# MolkkyV2.net
KiCad netlist of a schematic drawn in Altium Designer
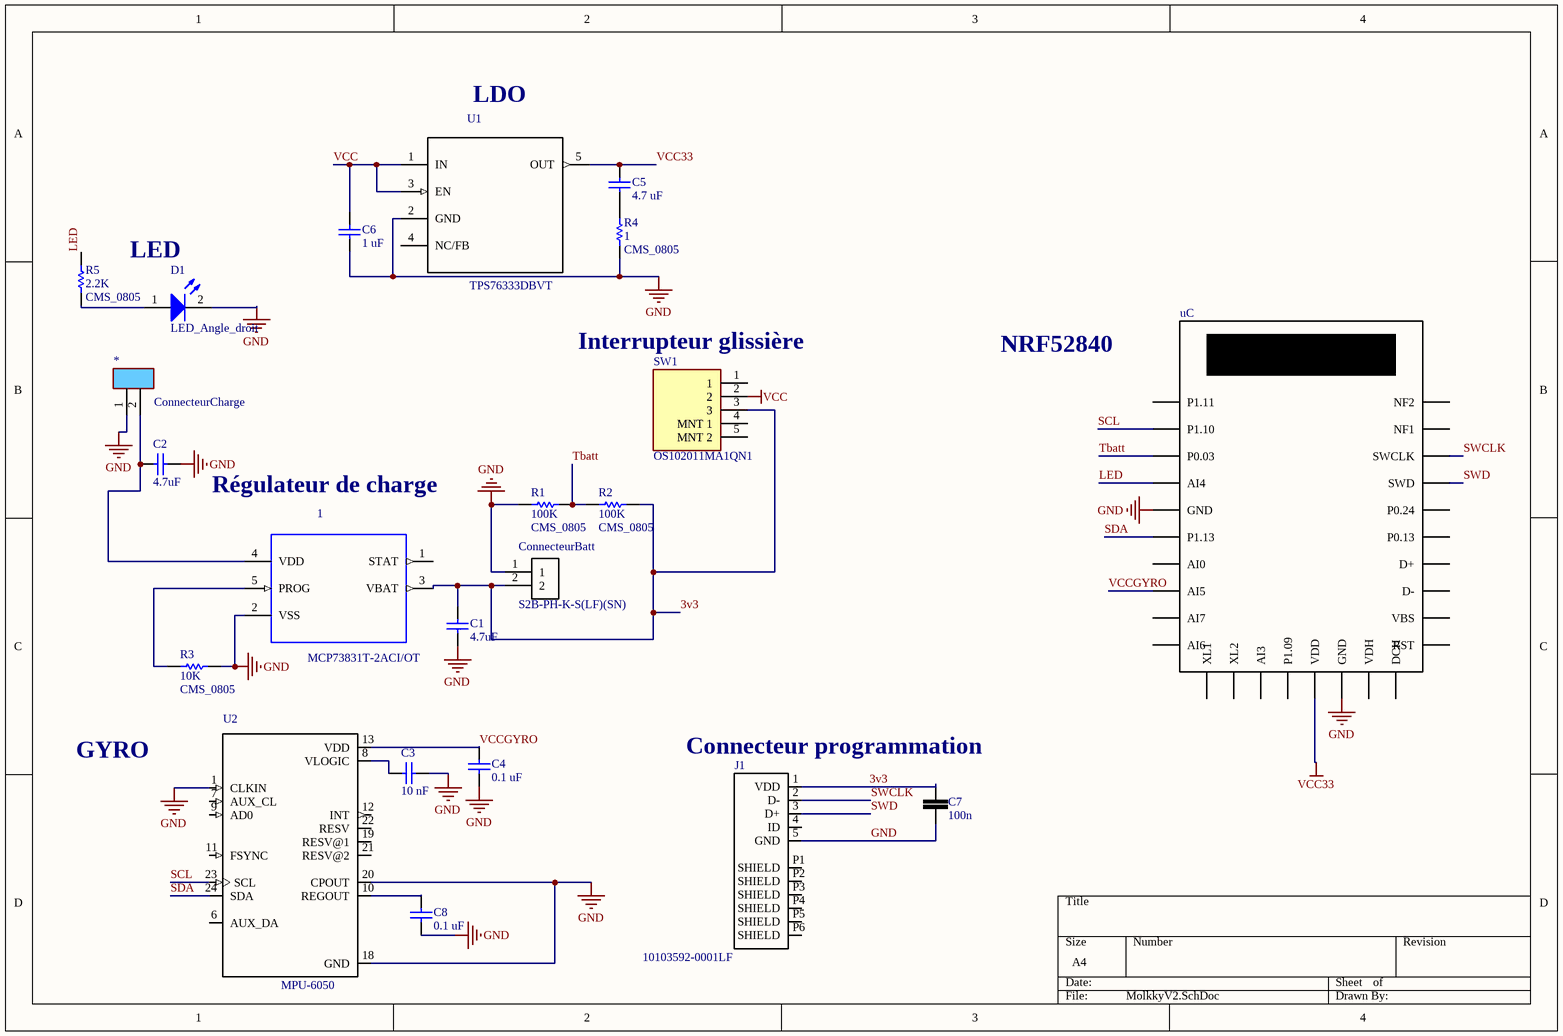
[diagram p0: MolkkyV2.SchDoc]

(export (version "E")
  (design (tool "Eeschema 10.0.6"))
  (components
    (comp (ref "*")
      (value "ConnecteurCharge")
      (footprint "BARRETTE 2")
      (libsource (lib "connecteurs") (part "Barrette 2"))
    )
    (comp (ref "1")
      (value "MCP73831T-2ACI/OT")
      (footprint "*SOT95P280X145-5N")
      (description "MCP73831 Series Single-Cell Li-Ion/Li-Polymer Battery Charge Controller SOT-23-5")
      (fields (field (name "MF") "Microchip"))
      (libsource (lib "MCP73831T-2ACI_OT") (part "MCP73831T-2ACI/OT"))
    )
    (comp (ref "C1")
      (value "4.7uF")
      (footprint "CONDENSATEUR_CMS_0805")
      (description "CONDENSATEUR CMS CERAMIQUE 0805")
      (fields (field (name "Comment") "CMS_0805"))
      (libsource (lib "composants passifs") (part "CONDENSATEUR_CMS_CER_0805"))
    )
    (comp (ref "C2")
      (value "4.7uF")
      (footprint "CONDENSATEUR_CMS_0805")
      (description "CONDENSATEUR CMS CERAMIQUE 0805")
      (fields (field (name "Comment") "CMS_0805"))
      (libsource (lib "composants passifs") (part "CONDENSATEUR_CMS_CER_0805"))
    )
    (comp (ref "C3")
      (value "10 nF")
      (footprint "CONDENSATEUR_CMS_0805")
      (description "CONDENSATEUR CMS CERAMIQUE 0805")
      (fields (field (name "Comment") "CMS_0805"))
      (libsource (lib "composants passifs") (part "CONDENSATEUR_CMS_CER_0805"))
    )
    (comp (ref "C4")
      (value "0.1 uF")
      (footprint "CONDENSATEUR_CMS_0805")
      (description "CONDENSATEUR CMS CERAMIQUE 0805")
      (fields (field (name "Comment") "CMS_0805"))
      (libsource (lib "composants passifs") (part "CONDENSATEUR_CMS_CER_0805"))
    )
    (comp (ref "C5")
      (value "4.7 uF")
      (footprint "CONDENSATEUR_CMS_0805")
      (description "CONDENSATEUR CMS CERAMIQUE 0805")
      (fields (field (name "Comment") "CMS_0805"))
      (libsource (lib "composants passifs") (part "CONDENSATEUR_CMS_CER_0805"))
    )
    (comp (ref "C6")
      (value "1 uF")
      (footprint "CONDENSATEUR_CMS_0805")
      (description "CONDENSATEUR CMS CERAMIQUE 0805")
      (fields (field (name "Comment") "CMS_0805"))
      (libsource (lib "composants passifs") (part "CONDENSATEUR_CMS_CER_0805"))
    )
    (comp (ref "C7")
      (value "100n")
      (footprint "CAPC2013X100N-0805-NoOverlay")
      (fields
        (field (name "MANUFACTURER") "Yageo")
        (field (name "MANUFACTURER PART NUMBER") "CC0805KRX7R9BB104")
        (field (name "TOLERANCE") "10%")
      )
      (libsource (lib "capacitors") (part "0100000001868"))
    )
    (comp (ref "C8")
      (value "0.1 uF")
      (footprint "CONDENSATEUR_CMS_0805")
      (description "CONDENSATEUR CMS CERAMIQUE 0805")
      (fields (field (name "Comment") "CMS_0805"))
      (libsource (lib "composants passifs") (part "CONDENSATEUR_CMS_CER_0805"))
    )
    (comp (ref "ConnecteurBatt")
      (value "S2B-PH-K-S(LF)(SN)")
      (footprint "*JST_S2B-PH-K-S(LF)(SN)")
      (description "PH Series 2 Position 2.0 mm Through Hole Side Entry Shrouded Header")
      (fields (field (name "MP") "S2B-PH-K-S_LF__SN_") (field (name "MF") "JST Sales"))
      (libsource (lib "S2B-PH-K-S_LF__SN_") (part "S2B-PH-K-S(LF)(SN)"))
    )
    (comp (ref "D1")
      (value "LED_3MM")
      (footprint "LED_Angle_droit")
      (description "LED Angle droit - ROUGE")
      (fields (field (name "TYPE") "LED_Angle_droit"))
      (libsource (lib "affichage") (part "LED Angle droit"))
    )
    (comp (ref "J1")
      (value "10103592-0001LF")
      (footprint "*AMPHENOL_10103592-0001LF_10103592-0001LF(Primary)")
      (description "Micro Usb, 2.0 Type b, Rcpt, Smt")
      (fields (field (name "MF") "Amphenol ICC"))
      (libsource (lib "10103592-0001LF") (part "10103592-0001LF"))
    )
    (comp (ref "R1")
      (value "100K")
      (footprint "RESISTANCE_CMS_0805")
      (description "RESISTANCE CMS 0805")
      (fields (field (name "TYPE") "CMS_0805") (field (name "Comment") "RESISTANCE_CMS_0805"))
      (libsource (lib "composants passifs") (part "RESISTANCE_CMS_0805"))
    )
    (comp (ref "R2")
      (value "100K")
      (footprint "RESISTANCE_CMS_0805")
      (description "RESISTANCE CMS 0805")
      (fields (field (name "TYPE") "CMS_0805") (field (name "Comment") "RESISTANCE_CMS_0805"))
      (libsource (lib "composants passifs") (part "RESISTANCE_CMS_0805"))
    )
    (comp (ref "R3")
      (value "10K")
      (footprint "RESISTANCE_CMS_0805")
      (description "RESISTANCE CMS 0805")
      (fields (field (name "TYPE") "CMS_0805") (field (name "Comment") "RESISTANCE_CMS_0805"))
      (libsource (lib "composants passifs") (part "RESISTANCE_CMS_0805"))
    )
    (comp (ref "R4")
      (value "1")
      (footprint "RESISTANCE_CMS_0805")
      (description "RESISTANCE CMS 0805")
      (fields (field (name "TYPE") "CMS_0805") (field (name "Comment") "RESISTANCE_CMS_0805"))
      (libsource (lib "composants passifs") (part "RESISTANCE_CMS_0805"))
    )
    (comp (ref "R5")
      (value "2.2K")
      (footprint "RESISTANCE_CMS_0805")
      (description "RESISTANCE CMS 0805")
      (fields (field (name "TYPE") "CMS_0805") (field (name "Comment") "RESISTANCE_CMS_0805"))
      (libsource (lib "composants passifs") (part "RESISTANCE_CMS_0805"))
    )
    (comp (ref "SW1")
      (value "Switch_C&K_OS102011MA1QN1_eec")
      (footprint "C&K_OS102011MA1QN1_0")
      (description "SWITCH SLIDE SPDT 100MA 12V")
      (fields
        (field (name "PART NUMBER") "OS102011MA1QN1")
        (field (name "MANUFACTURER") "C&K")
        (field (name "MOUSER PART NUMBER") "OS102011MA1QN1")
      )
      (libsource (lib "Switch_C&K_OS102011MA1QN1_eec") (part "Switch_C&K_OS102011MA1QN1_eec"))
    )
    (comp (ref "U1")
      (value "TPS76333DBVT")
      (footprint "*SOT95P280X145-5N")
      (description "LDO voltage regulator [Texas Instruments] TPS76333DBVT LDO voltage regulator")
      (fields (field (name "MF") "Texas Instruments"))
      (libsource (lib "TPS76333DBVT") (part "TPS76333DBVT"))
    )
    (comp (ref "U2")
      (value "MPU-6050")
      (footprint "*QFN50P400X400X95-24N")
      (description "3-axis gyroscope, 3-axis accelerometer in a 4x4x0.9 housing")
      (fields (field (name "MF") "TDK InvenSense"))
      (libsource (lib "MPU-6050") (part "MPU-6050"))
    )
    (comp (ref "uC")
      (value "NRF52840 kit")
      (footprint "uC_NRF52840")
      (libsource (lib "Molk") (part "NRF52840 kit"))
    )
  )
  (nets
    (net (code "1") (name "/3v3") (class "Default")
      (node (ref "1") (pin "3") (pinfunction "VBAT_3") (pintype "output"))
      (node (ref "C1") (pin "2") (pinfunction "2_2") (pintype "passive"))
      (node (ref "C7") (pin "2") (pinfunction "2_2") (pintype "passive"))
      (node (ref "ConnecteurBatt") (pin "2") (pinfunction "2_2") (pintype "passive"))
      (node (ref "J1") (pin "1") (pinfunction "VDD_1") (pintype "power_in"))
      (node (ref "R2") (pin "2") (pinfunction "2_2") (pintype "passive"))
      (node (ref "SW1") (pin "3") (pinfunction "3_3") (pintype "passive"))
    )
    (net (code "2") (name "/LED") (class "Default")
      (node (ref "R5") (pin "2") (pinfunction "2_2") (pintype "passive"))
      (node (ref "uC") (pin "4") (pinfunction "AI4_4") (pintype "passive"))
    )
    (net (code "3") (name "/SCL") (class "Default")
      (node (ref "U2") (pin "23") (pinfunction "SCL_23") (pintype "input"))
      (node (ref "uC") (pin "2") (pinfunction "P1.10_2") (pintype "passive"))
    )
    (net (code "4") (name "/SDA") (class "Default")
      (node (ref "U2") (pin "24") (pinfunction "SDA_24") (pintype "bidirectional"))
      (node (ref "uC") (pin "6") (pinfunction "P1.13_6") (pintype "passive"))
    )
    (net (code "5") (name "/SWCLK") (class "Default")
      (node (ref "J1") (pin "2") (pinfunction "D-_2") (pintype "bidirectional"))
      (node (ref "uC") (pin "28") (pinfunction "SWCLK_28") (pintype "passive"))
    )
    (net (code "6") (name "/SWD") (class "Default")
      (node (ref "J1") (pin "3") (pinfunction "D+_3") (pintype "bidirectional"))
      (node (ref "uC") (pin "27") (pinfunction "SWD_27") (pintype "passive"))
    )
    (net (code "7") (name "/Tbatt") (class "Default")
      (node (ref "R1") (pin "2") (pinfunction "2_2") (pintype "passive"))
      (node (ref "R2") (pin "1") (pinfunction "1_1") (pintype "passive"))
      (node (ref "uC") (pin "3") (pinfunction "P0.03_3") (pintype "passive"))
    )
    (net (code "8") (name "/VCCGYRO") (class "Default")
      (node (ref "C4") (pin "1") (pinfunction "1_1") (pintype "passive"))
      (node (ref "U2") (pin "13") (pinfunction "VDD_13") (pintype "power_in"))
      (node (ref "uC") (pin "8") (pinfunction "AI5_8") (pintype "passive"))
    )
    (net (code "9") (name "GND") (class "Default")
      (node (ref "*") (pin "1") (pinfunction "1_1") (pintype "passive"))
      (node (ref "1") (pin "2") (pinfunction "VSS_2") (pintype "power_in"))
      (node (ref "C1") (pin "1") (pinfunction "1_1") (pintype "passive"))
      (node (ref "C2") (pin "1") (pinfunction "1_1") (pintype "passive"))
      (node (ref "C3") (pin "2") (pinfunction "2_2") (pintype "passive"))
      (node (ref "C4") (pin "2") (pinfunction "2_2") (pintype "passive"))
      (node (ref "C6") (pin "2") (pinfunction "2_2") (pintype "passive"))
      (node (ref "C7") (pin "1") (pinfunction "1_1") (pintype "passive"))
      (node (ref "C8") (pin "2") (pinfunction "2_2") (pintype "passive"))
      (node (ref "ConnecteurBatt") (pin "1") (pinfunction "1_1") (pintype "passive"))
      (node (ref "D1") (pin "2") (pinfunction "2_2") (pintype "passive"))
      (node (ref "J1") (pin "5") (pinfunction "GND_5") (pintype "power_in"))
      (node (ref "R1") (pin "1") (pinfunction "1_1") (pintype "passive"))
      (node (ref "R3") (pin "2") (pinfunction "2_2") (pintype "passive"))
      (node (ref "R4") (pin "1") (pinfunction "1_1") (pintype "passive"))
      (node (ref "U1") (pin "2") (pinfunction "GND_2") (pintype "passive"))
      (node (ref "U2") (pin "1") (pinfunction "CLKIN_1") (pintype "input"))
      (node (ref "U2") (pin "18") (pinfunction "GND_18") (pintype "power_in"))
      (node (ref "U2") (pin "20") (pinfunction "CPOUT_20") (pintype "passive"))
      (node (ref "uC") (pin "16") (pinfunction "GND_16") (pintype "passive"))
      (node (ref "uC") (pin "5") (pinfunction "GND_5") (pintype "passive"))
    )
    (net (code "10") (name "Net-(1-PROG)") (class "Default")
      (node (ref "1") (pin "5") (pinfunction "PROG_5") (pintype "input"))
      (node (ref "R3") (pin "1") (pinfunction "1_1") (pintype "passive"))
    )
    (net (code "11") (name "Net-(1-VDD)") (class "Default")
      (node (ref "*") (pin "2") (pinfunction "2_2") (pintype "passive"))
      (node (ref "1") (pin "4") (pinfunction "VDD_4") (pintype "power_in"))
      (node (ref "C2") (pin "2") (pinfunction "2_2") (pintype "passive"))
    )
    (net (code "12") (name "Net-(C5-Pad2)") (class "Default")
      (node (ref "C5") (pin "2") (pinfunction "2_2") (pintype "passive"))
      (node (ref "R4") (pin "2") (pinfunction "2_2") (pintype "passive"))
    )
    (net (code "13") (name "Net-(D1-Pad1)") (class "Default")
      (node (ref "D1") (pin "1") (pinfunction "1_1") (pintype "passive"))
      (node (ref "R5") (pin "1") (pinfunction "1_1") (pintype "passive"))
    )
    (net (code "14") (name "Net-(U2-REGOUT)") (class "Default")
      (node (ref "C8") (pin "1") (pinfunction "1_1") (pintype "passive"))
      (node (ref "U2") (pin "10") (pinfunction "REGOUT_10") (pintype "passive"))
    )
    (net (code "15") (name "Net-(U2-VLOGIC)") (class "Default")
      (node (ref "C3") (pin "1") (pinfunction "1_1") (pintype "passive"))
      (node (ref "U2") (pin "8") (pinfunction "VLOGIC_8") (pintype "power_in"))
    )
    (net (code "16") (name "VCC") (class "Default")
      (node (ref "C6") (pin "1") (pinfunction "1_1") (pintype "passive"))
      (node (ref "SW1") (pin "2") (pinfunction "2_2") (pintype "passive"))
      (node (ref "U1") (pin "1") (pinfunction "IN_1") (pintype "power_in"))
      (node (ref "U1") (pin "3") (pinfunction "EN_3") (pintype "input"))
    )
    (net (code "17") (name "VCC33") (class "Default")
      (node (ref "C5") (pin "1") (pinfunction "1_1") (pintype "passive"))
      (node (ref "U1") (pin "5") (pinfunction "OUT_5") (pintype "output"))
      (node (ref "uC") (pin "15") (pinfunction "VDD_15") (pintype "passive"))
    )
    (net (code "18") (name "unconnected-(1-STAT-Pad1)") (class "Default")
      (node (ref "1") (pin "1") (pinfunction "STAT_1") (pintype "output"))
    )
    (net (code "19") (name "unconnected-(J1-ID-Pad4)") (class "Default")
      (node (ref "J1") (pin "4") (pinfunction "ID_4") (pintype "bidirectional"))
    )
    (net (code "20") (name "unconnected-(J1-SHIELD-PadP1)") (class "Default")
      (node (ref "J1") (pin "P1") (pinfunction "SHIELD_P1") (pintype "power_in"))
    )
    (net (code "21") (name "unconnected-(J1-SHIELD-PadP2)") (class "Default")
      (node (ref "J1") (pin "P2") (pinfunction "SHIELD_P2") (pintype "power_in"))
    )
    (net (code "22") (name "unconnected-(J1-SHIELD-PadP3)") (class "Default")
      (node (ref "J1") (pin "P3") (pinfunction "SHIELD_P3") (pintype "power_in"))
    )
    (net (code "23") (name "unconnected-(J1-SHIELD-PadP4)") (class "Default")
      (node (ref "J1") (pin "P4") (pinfunction "SHIELD_P4") (pintype "power_in"))
    )
    (net (code "24") (name "unconnected-(J1-SHIELD-PadP5)") (class "Default")
      (node (ref "J1") (pin "P5") (pinfunction "SHIELD_P5") (pintype "power_in"))
    )
    (net (code "25") (name "unconnected-(J1-SHIELD-PadP6)") (class "Default")
      (node (ref "J1") (pin "P6") (pinfunction "SHIELD_P6") (pintype "power_in"))
    )
    (net (code "26") (name "unconnected-(SW1-MNT_1-Pad4)") (class "Default")
      (node (ref "SW1") (pin "4") (pinfunction "MNT_1_4") (pintype "passive"))
    )
    (net (code "27") (name "unconnected-(SW1-MNT_2-Pad5)") (class "Default")
      (node (ref "SW1") (pin "5") (pinfunction "MNT_2_5") (pintype "passive"))
    )
    (net (code "28") (name "unconnected-(SW1-Pad1)") (class "Default")
      (node (ref "SW1") (pin "1") (pinfunction "1_1") (pintype "passive"))
    )
    (net (code "29") (name "unconnected-(U1-NC{slash}FB-Pad4)") (class "Default")
      (node (ref "U1") (pin "4") (pinfunction "NC/FB_4") (pintype "passive"))
    )
    (net (code "30") (name "unconnected-(U2-AD0-Pad9)") (class "Default")
      (node (ref "U2") (pin "9") (pinfunction "AD0_9") (pintype "input"))
    )
    (net (code "31") (name "unconnected-(U2-AUX_CL-Pad7)") (class "Default")
      (node (ref "U2") (pin "7") (pinfunction "AUX_CL_7") (pintype "input"))
    )
    (net (code "32") (name "unconnected-(U2-AUX_DA-Pad6)") (class "Default")
      (node (ref "U2") (pin "6") (pinfunction "AUX_DA_6") (pintype "bidirectional"))
    )
    (net (code "33") (name "unconnected-(U2-FSYNC-Pad11)") (class "Default")
      (node (ref "U2") (pin "11") (pinfunction "FSYNC_11") (pintype "input"))
    )
    (net (code "34") (name "unconnected-(U2-INT-Pad12)") (class "Default")
      (node (ref "U2") (pin "12") (pinfunction "INT_12") (pintype "output"))
    )
    (net (code "35") (name "unconnected-(U2-RESV-Pad22)") (class "Default")
      (node (ref "U2") (pin "22") (pinfunction "RESV_22") (pintype "passive"))
    )
    (net (code "36") (name "unconnected-(U2-RESV@1-Pad19)") (class "Default")
      (node (ref "U2") (pin "19") (pinfunction "RESV@1_19") (pintype "passive"))
    )
    (net (code "37") (name "unconnected-(U2-RESV@2-Pad21)") (class "Default")
      (node (ref "U2") (pin "21") (pinfunction "RESV@2_21") (pintype "passive"))
    )
    (net (code "38") (name "unconnected-(uC-AI0-Pad7)") (class "Default")
      (node (ref "uC") (pin "7") (pinfunction "AI0_7") (pintype "passive"))
    )
    (net (code "39") (name "unconnected-(uC-AI3-Pad13)") (class "Default")
      (node (ref "uC") (pin "13") (pinfunction "AI3_13") (pintype "passive"))
    )
    (net (code "40") (name "unconnected-(uC-AI6-Pad10)") (class "Default")
      (node (ref "uC") (pin "10") (pinfunction "AI6_10") (pintype "passive"))
    )
    (net (code "41") (name "unconnected-(uC-AI7-Pad9)") (class "Default")
      (node (ref "uC") (pin "9") (pinfunction "AI7_9") (pintype "passive"))
    )
    (net (code "42") (name "unconnected-(uC-D+-Pad24)") (class "Default")
      (node (ref "uC") (pin "24") (pinfunction "D+_24") (pintype "passive"))
    )
    (net (code "43") (name "unconnected-(uC-D--Pad23)") (class "Default")
      (node (ref "uC") (pin "23") (pinfunction "D-_23") (pintype "passive"))
    )
    (net (code "44") (name "unconnected-(uC-DCH-Pad18)") (class "Default")
      (node (ref "uC") (pin "18") (pinfunction "DCH_18") (pintype "passive"))
    )
    (net (code "45") (name "unconnected-(uC-NF1-Pad29)") (class "Default")
      (node (ref "uC") (pin "29") (pinfunction "NF1_29") (pintype "passive"))
    )
    (net (code "46") (name "unconnected-(uC-NF2-Pad30)") (class "Default")
      (node (ref "uC") (pin "30") (pinfunction "NF2_30") (pintype "passive"))
    )
    (net (code "47") (name "unconnected-(uC-P0.13-Pad25)") (class "Default")
      (node (ref "uC") (pin "25") (pinfunction "P0.13_25") (pintype "passive"))
    )
    (net (code "48") (name "unconnected-(uC-P0.24-Pad26)") (class "Default")
      (node (ref "uC") (pin "26") (pinfunction "P0.24_26") (pintype "passive"))
    )
    (net (code "49") (name "unconnected-(uC-P1.09-Pad14)") (class "Default")
      (node (ref "uC") (pin "14") (pinfunction "P1.09_14") (pintype "passive"))
    )
    (net (code "50") (name "unconnected-(uC-P1.11-Pad1)") (class "Default")
      (node (ref "uC") (pin "1") (pinfunction "P1.11_1") (pintype "passive"))
    )
    (net (code "51") (name "unconnected-(uC-RST-Pad21)") (class "Default")
      (node (ref "uC") (pin "21") (pinfunction "RST_21") (pintype "passive"))
    )
    (net (code "52") (name "unconnected-(uC-VBS-Pad22)") (class "Default")
      (node (ref "uC") (pin "22") (pinfunction "VBS_22") (pintype "passive"))
    )
    (net (code "53") (name "unconnected-(uC-VDH-Pad17)") (class "Default")
      (node (ref "uC") (pin "17") (pinfunction "VDH_17") (pintype "passive"))
    )
    (net (code "54") (name "unconnected-(uC-XL1-Pad11)") (class "Default")
      (node (ref "uC") (pin "11") (pinfunction "XL1_11") (pintype "passive"))
    )
    (net (code "55") (name "unconnected-(uC-XL2-Pad12)") (class "Default")
      (node (ref "uC") (pin "12") (pinfunction "XL2_12") (pintype "passive"))
    )
  )
)
